# anet-esp8266-ext-mirrored.net
KiCad netlist of a schematic drawn in EAGLE
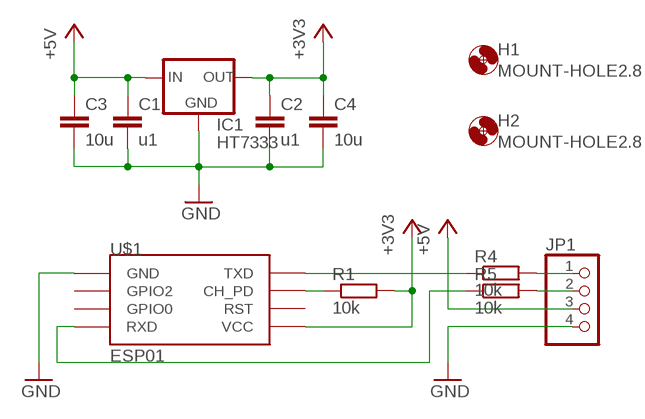
[diagram p0: schematic, sheet 1]

(export (version "E")
  (design (tool "Eeschema 10.0.6"))
  (components
    (comp (ref "C1")
      (value "u1")
      (footprint "eagle-import:C0805")
      (libsource (lib "eagle-import") (part "C-EUC0805"))
    )
    (comp (ref "C2")
      (value "u1")
      (footprint "eagle-import:C0805K")
      (libsource (lib "eagle-import") (part "C-EUC0805K"))
    )
    (comp (ref "C3")
      (value "10u")
      (footprint "eagle-import:C0805K")
      (libsource (lib "eagle-import") (part "C-EUC0805K"))
    )
    (comp (ref "C4")
      (value "10u")
      (footprint "eagle-import:C0805K")
      (libsource (lib "eagle-import") (part "C-EUC0805K"))
    )
    (comp (ref "H1")
      (value "MOUNT-HOLE2.8")
      (footprint "eagle-import:2,8")
      (libsource (lib "eagle-import") (part "MOUNT-HOLE2.8"))
    )
    (comp (ref "H2")
      (value "MOUNT-HOLE2.8")
      (footprint "eagle-import:2,8")
      (libsource (lib "eagle-import") (part "MOUNT-HOLE2.8"))
    )
    (comp (ref "IC1")
      (value "HT7333")
      (footprint "eagle-import:SOT-89")
      (libsource (lib "eagle-import") (part "HT7333"))
    )
    (comp (ref "JP1")
      (value "PINHD-1X4")
      (footprint "eagle-import:1X04")
      (libsource (lib "eagle-import") (part "PINHD-1X4"))
    )
    (comp (ref "R1")
      (value "10k")
      (footprint "eagle-import:M0805")
      (libsource (lib "eagle-import") (part "R-EU_M0805"))
    )
    (comp (ref "R4")
      (value "10k")
      (footprint "eagle-import:R0805")
      (libsource (lib "eagle-import") (part "R-EU_R0805"))
    )
    (comp (ref "R5")
      (value "10k")
      (footprint "eagle-import:M0805")
      (libsource (lib "eagle-import") (part "R-EU_M0805"))
    )
    (comp (ref "U$1")
      (value "ESP01")
      (footprint "eagle-import:ESP01")
      (libsource (lib "eagle-import") (part "ESP01"))
    )
  )
  (nets
    (net (code "1") (name "+3V3") (class "Default")
      (node (ref "C2") (pin "1") (pinfunction "1_1") (pintype "passive"))
      (node (ref "C4") (pin "1") (pinfunction "1_1") (pintype "passive"))
      (node (ref "IC1") (pin "1") (pinfunction "OUT_1") (pintype "passive"))
      (node (ref "R1") (pin "2") (pinfunction "2_2") (pintype "passive"))
      (node (ref "U$1") (pin "VCC") (pinfunction "VCC_VCC") (pintype "bidirectional"))
    )
    (net (code "2") (name "+5V") (class "Default")
      (node (ref "C1") (pin "1") (pinfunction "1_1") (pintype "passive"))
      (node (ref "C3") (pin "1") (pinfunction "1_1") (pintype "passive"))
      (node (ref "IC1") (pin "3") (pinfunction "IN_3") (pintype "input"))
      (node (ref "IC1") (pin "4") (pinfunction "IN_4") (pintype "input"))
      (node (ref "JP1") (pin "3") (pinfunction "3_3") (pintype "passive"))
    )
    (net (code "3") (name "GND") (class "Default")
      (node (ref "C1") (pin "2") (pinfunction "2_2") (pintype "passive"))
      (node (ref "C2") (pin "2") (pinfunction "2_2") (pintype "passive"))
      (node (ref "C3") (pin "2") (pinfunction "2_2") (pintype "passive"))
      (node (ref "C4") (pin "2") (pinfunction "2_2") (pintype "passive"))
      (node (ref "IC1") (pin "2") (pinfunction "GND_2") (pintype "input"))
      (node (ref "JP1") (pin "4") (pinfunction "4_4") (pintype "passive"))
      (node (ref "U$1") (pin "GND") (pinfunction "GND_GND") (pintype "bidirectional"))
    )
    (net (code "4") (name "Net-(JP1-Pad1)") (class "Default")
      (node (ref "JP1") (pin "1") (pinfunction "1_1") (pintype "passive"))
      (node (ref "R4") (pin "2") (pinfunction "2_2") (pintype "passive"))
    )
    (net (code "5") (name "Net-(JP1-Pad2)") (class "Default")
      (node (ref "JP1") (pin "2") (pinfunction "2_2") (pintype "passive"))
      (node (ref "R5") (pin "2") (pinfunction "2_2") (pintype "passive"))
    )
    (net (code "6") (name "Net-(R1-Pad1)") (class "Default")
      (node (ref "R1") (pin "1") (pinfunction "1_1") (pintype "passive"))
      (node (ref "U$1") (pin "CH_PD") (pinfunction "CH_PD_CH_PD") (pintype "bidirectional"))
    )
    (net (code "7") (name "Net-(U$1-RXD)") (class "Default")
      (node (ref "R5") (pin "1") (pinfunction "1_1") (pintype "passive"))
      (node (ref "U$1") (pin "RX") (pinfunction "RXD_RX") (pintype "bidirectional"))
    )
    (net (code "8") (name "Net-(U$1-TXD)") (class "Default")
      (node (ref "R4") (pin "1") (pinfunction "1_1") (pintype "passive"))
      (node (ref "U$1") (pin "TX") (pinfunction "TXD_TX") (pintype "bidirectional"))
    )
    (net (code "9") (name "unconnected-(U$1-PadGPIO0)") (class "Default")
      (node (ref "U$1") (pin "GPIO0") (pinfunction "GPIO0_GPIO0") (pintype "bidirectional"))
    )
    (net (code "10") (name "unconnected-(U$1-PadGPIO2)") (class "Default")
      (node (ref "U$1") (pin "GPIO2") (pinfunction "GPIO2_GPIO2") (pintype "bidirectional"))
    )
    (net (code "11") (name "unconnected-(U$1-PadRST)") (class "Default")
      (node (ref "U$1") (pin "RST") (pinfunction "RST_RST") (pintype "bidirectional"))
    )
  )
)
